# ADE7880_Breakout.net
KiCad netlist of a schematic drawn in EAGLE
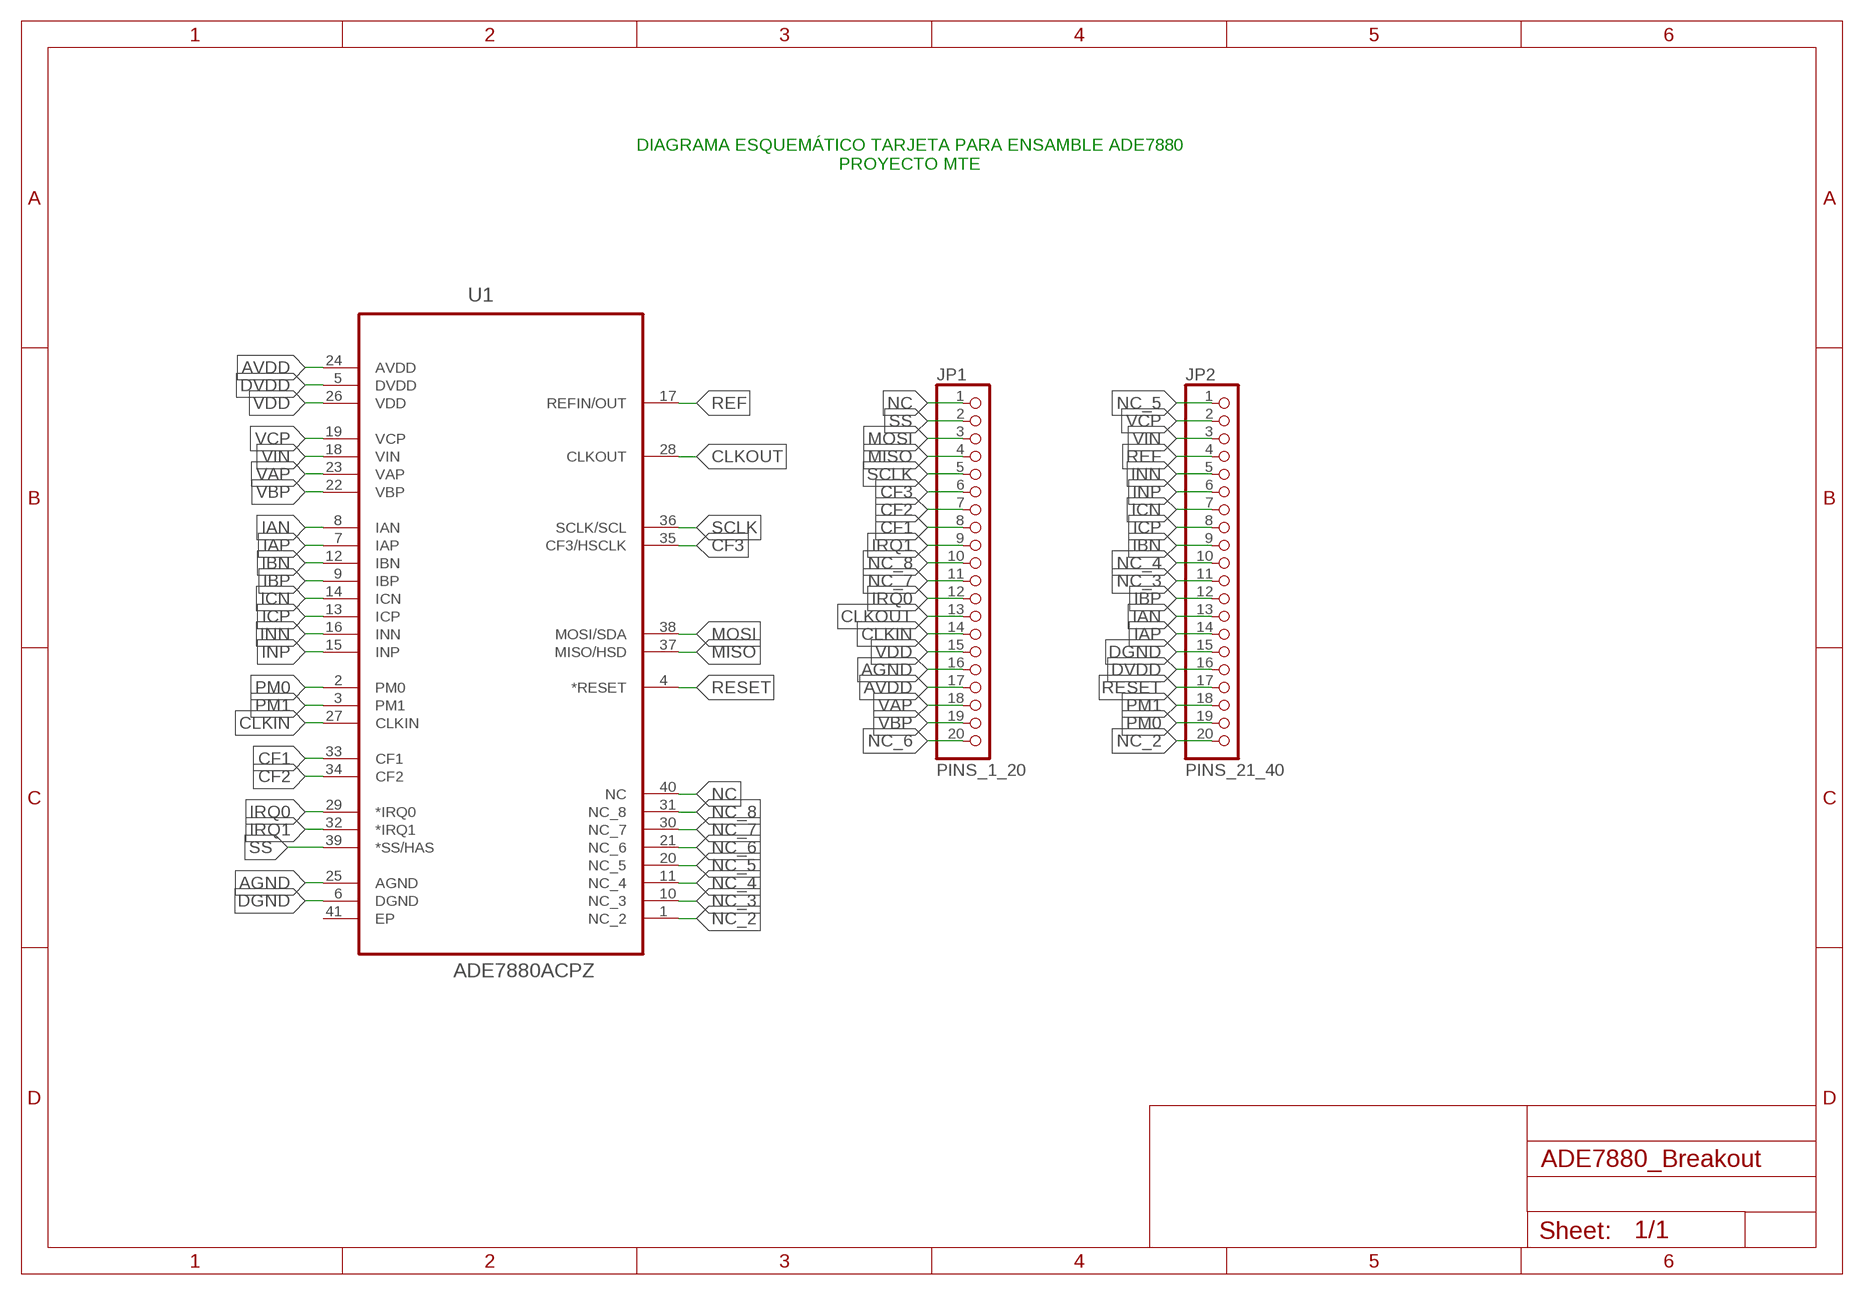
[diagram p0: schematic, sheet 1]

(export (version "E")
  (design (tool "Eeschema 10.0.6"))
  (components
    (comp (ref "JP1")
      (value "PINS_1_20")
      (footprint "eagle-import:1X20")
      (libsource (lib "eagle-import") (part "PINHD-1X20"))
    )
    (comp (ref "JP2")
      (value "PINS_21_40")
      (footprint "eagle-import:1X20")
      (libsource (lib "eagle-import") (part "PINHD-1X20"))
    )
    (comp (ref "U1")
      (value "ADE7880ACPZ")
      (footprint "eagle-import:QFN50P600X600X80-41N")
      (fields (field (name "MF") "Analog Devices"))
      (libsource (lib "eagle-import") (part "ADE7880ACPZ"))
    )
  )
  (nets
    (net (code "1") (name "AGND") (class "Default")
      (node (ref "JP1") (pin "16") (pinfunction "16_16") (pintype "passive"))
      (node (ref "U1") (pin "25") (pinfunction "AGND_25") (pintype "passive"))
    )
    (net (code "2") (name "AVDD") (class "Default")
      (node (ref "JP1") (pin "17") (pinfunction "17_17") (pintype "passive"))
      (node (ref "U1") (pin "24") (pinfunction "AVDD_24") (pintype "passive"))
    )
    (net (code "3") (name "CF1") (class "Default")
      (node (ref "JP1") (pin "8") (pinfunction "8_8") (pintype "passive"))
      (node (ref "U1") (pin "33") (pinfunction "CF1_33") (pintype "passive"))
    )
    (net (code "4") (name "CF2") (class "Default")
      (node (ref "JP1") (pin "7") (pinfunction "7_7") (pintype "passive"))
      (node (ref "U1") (pin "34") (pinfunction "CF2_34") (pintype "passive"))
    )
    (net (code "5") (name "CF3") (class "Default")
      (node (ref "JP1") (pin "6") (pinfunction "6_6") (pintype "passive"))
      (node (ref "U1") (pin "35") (pinfunction "CF3/HSCLK_35") (pintype "passive"))
    )
    (net (code "6") (name "CLKIN") (class "Default")
      (node (ref "JP1") (pin "14") (pinfunction "14_14") (pintype "passive"))
      (node (ref "U1") (pin "27") (pinfunction "CLKIN_27") (pintype "passive"))
    )
    (net (code "7") (name "CLKOUT") (class "Default")
      (node (ref "JP1") (pin "13") (pinfunction "13_13") (pintype "passive"))
      (node (ref "U1") (pin "28") (pinfunction "CLKOUT_28") (pintype "passive"))
    )
    (net (code "8") (name "DGND") (class "Default")
      (node (ref "JP2") (pin "15") (pinfunction "15_15") (pintype "passive"))
      (node (ref "U1") (pin "6") (pinfunction "DGND_6") (pintype "passive"))
    )
    (net (code "9") (name "DVDD") (class "Default")
      (node (ref "JP2") (pin "16") (pinfunction "16_16") (pintype "passive"))
      (node (ref "U1") (pin "5") (pinfunction "DVDD_5") (pintype "passive"))
    )
    (net (code "10") (name "IAN") (class "Default")
      (node (ref "JP2") (pin "13") (pinfunction "13_13") (pintype "passive"))
      (node (ref "U1") (pin "8") (pinfunction "IAN_8") (pintype "passive"))
    )
    (net (code "11") (name "IAP") (class "Default")
      (node (ref "JP2") (pin "14") (pinfunction "14_14") (pintype "passive"))
      (node (ref "U1") (pin "7") (pinfunction "IAP_7") (pintype "passive"))
    )
    (net (code "12") (name "IBN") (class "Default")
      (node (ref "JP2") (pin "9") (pinfunction "9_9") (pintype "passive"))
      (node (ref "U1") (pin "12") (pinfunction "IBN_12") (pintype "passive"))
    )
    (net (code "13") (name "IBP") (class "Default")
      (node (ref "JP2") (pin "12") (pinfunction "12_12") (pintype "passive"))
      (node (ref "U1") (pin "9") (pinfunction "IBP_9") (pintype "passive"))
    )
    (net (code "14") (name "ICN") (class "Default")
      (node (ref "JP2") (pin "7") (pinfunction "7_7") (pintype "passive"))
      (node (ref "U1") (pin "14") (pinfunction "ICN_14") (pintype "passive"))
    )
    (net (code "15") (name "ICP") (class "Default")
      (node (ref "JP2") (pin "8") (pinfunction "8_8") (pintype "passive"))
      (node (ref "U1") (pin "13") (pinfunction "ICP_13") (pintype "passive"))
    )
    (net (code "16") (name "INN") (class "Default")
      (node (ref "JP2") (pin "5") (pinfunction "5_5") (pintype "passive"))
      (node (ref "U1") (pin "16") (pinfunction "INN_16") (pintype "passive"))
    )
    (net (code "17") (name "INP") (class "Default")
      (node (ref "JP2") (pin "6") (pinfunction "6_6") (pintype "passive"))
      (node (ref "U1") (pin "15") (pinfunction "INP_15") (pintype "passive"))
    )
    (net (code "18") (name "IRQ0") (class "Default")
      (node (ref "JP1") (pin "12") (pinfunction "12_12") (pintype "passive"))
      (node (ref "U1") (pin "29") (pinfunction "*IRQ0_29") (pintype "passive"))
    )
    (net (code "19") (name "IRQ1") (class "Default")
      (node (ref "JP1") (pin "9") (pinfunction "9_9") (pintype "passive"))
      (node (ref "U1") (pin "32") (pinfunction "*IRQ1_32") (pintype "passive"))
    )
    (net (code "20") (name "MISO") (class "Default")
      (node (ref "JP1") (pin "4") (pinfunction "4_4") (pintype "passive"))
      (node (ref "U1") (pin "37") (pinfunction "MISO/HSD_37") (pintype "passive"))
    )
    (net (code "21") (name "MOSI") (class "Default")
      (node (ref "JP1") (pin "3") (pinfunction "3_3") (pintype "passive"))
      (node (ref "U1") (pin "38") (pinfunction "MOSI/SDA_38") (pintype "passive"))
    )
    (net (code "22") (name "NC") (class "Default")
      (node (ref "JP1") (pin "1") (pinfunction "1_1") (pintype "passive"))
      (node (ref "U1") (pin "40") (pinfunction "NC_40") (pintype "passive"))
    )
    (net (code "23") (name "NC_2") (class "Default")
      (node (ref "JP2") (pin "20") (pinfunction "20_20") (pintype "passive"))
      (node (ref "U1") (pin "1") (pinfunction "NC_2_1") (pintype "passive"))
    )
    (net (code "24") (name "NC_3") (class "Default")
      (node (ref "JP2") (pin "11") (pinfunction "11_11") (pintype "passive"))
      (node (ref "U1") (pin "10") (pinfunction "NC_3_10") (pintype "passive"))
    )
    (net (code "25") (name "NC_4") (class "Default")
      (node (ref "JP2") (pin "10") (pinfunction "10_10") (pintype "passive"))
      (node (ref "U1") (pin "11") (pinfunction "NC_4_11") (pintype "passive"))
    )
    (net (code "26") (name "NC_5") (class "Default")
      (node (ref "JP2") (pin "1") (pinfunction "1_1") (pintype "passive"))
      (node (ref "U1") (pin "20") (pinfunction "NC_5_20") (pintype "passive"))
    )
    (net (code "27") (name "NC_6") (class "Default")
      (node (ref "JP1") (pin "20") (pinfunction "20_20") (pintype "passive"))
      (node (ref "U1") (pin "21") (pinfunction "NC_6_21") (pintype "passive"))
    )
    (net (code "28") (name "NC_7") (class "Default")
      (node (ref "JP1") (pin "11") (pinfunction "11_11") (pintype "passive"))
      (node (ref "U1") (pin "30") (pinfunction "NC_7_30") (pintype "passive"))
    )
    (net (code "29") (name "NC_8") (class "Default")
      (node (ref "JP1") (pin "10") (pinfunction "10_10") (pintype "passive"))
      (node (ref "U1") (pin "31") (pinfunction "NC_8_31") (pintype "passive"))
    )
    (net (code "30") (name "PM0") (class "Default")
      (node (ref "JP2") (pin "19") (pinfunction "19_19") (pintype "passive"))
      (node (ref "U1") (pin "2") (pinfunction "PM0_2") (pintype "passive"))
    )
    (net (code "31") (name "PM1") (class "Default")
      (node (ref "JP2") (pin "18") (pinfunction "18_18") (pintype "passive"))
      (node (ref "U1") (pin "3") (pinfunction "PM1_3") (pintype "passive"))
    )
    (net (code "32") (name "REF") (class "Default")
      (node (ref "JP2") (pin "4") (pinfunction "4_4") (pintype "passive"))
      (node (ref "U1") (pin "17") (pinfunction "REFIN/OUT_17") (pintype "passive"))
    )
    (net (code "33") (name "RESET") (class "Default")
      (node (ref "JP2") (pin "17") (pinfunction "17_17") (pintype "passive"))
      (node (ref "U1") (pin "4") (pinfunction "*RESET_4") (pintype "passive"))
    )
    (net (code "34") (name "SCLK") (class "Default")
      (node (ref "JP1") (pin "5") (pinfunction "5_5") (pintype "passive"))
      (node (ref "U1") (pin "36") (pinfunction "SCLK/SCL_36") (pintype "passive"))
    )
    (net (code "35") (name "SS") (class "Default")
      (node (ref "JP1") (pin "2") (pinfunction "2_2") (pintype "passive"))
      (node (ref "U1") (pin "39") (pinfunction "*SS/HAS_39") (pintype "passive"))
    )
    (net (code "36") (name "VAP") (class "Default")
      (node (ref "JP1") (pin "18") (pinfunction "18_18") (pintype "passive"))
      (node (ref "U1") (pin "23") (pinfunction "VAP_23") (pintype "passive"))
    )
    (net (code "37") (name "VBP") (class "Default")
      (node (ref "JP1") (pin "19") (pinfunction "19_19") (pintype "passive"))
      (node (ref "U1") (pin "22") (pinfunction "VBP_22") (pintype "passive"))
    )
    (net (code "38") (name "VCP") (class "Default")
      (node (ref "JP2") (pin "2") (pinfunction "2_2") (pintype "passive"))
      (node (ref "U1") (pin "19") (pinfunction "VCP_19") (pintype "passive"))
    )
    (net (code "39") (name "VDD") (class "Default")
      (node (ref "JP1") (pin "15") (pinfunction "15_15") (pintype "passive"))
      (node (ref "U1") (pin "26") (pinfunction "VDD_26") (pintype "passive"))
    )
    (net (code "40") (name "VIN") (class "Default")
      (node (ref "JP2") (pin "3") (pinfunction "3_3") (pintype "passive"))
      (node (ref "U1") (pin "18") (pinfunction "VIN_18") (pintype "passive"))
    )
    (net (code "41") (name "unconnected-(U1-EP-Pad41)") (class "Default")
      (node (ref "U1") (pin "41") (pinfunction "EP_41") (pintype "passive"))
    )
  )
)
